# Relay_connected.net
KiCad netlist of a schematic drawn in Altium Designer
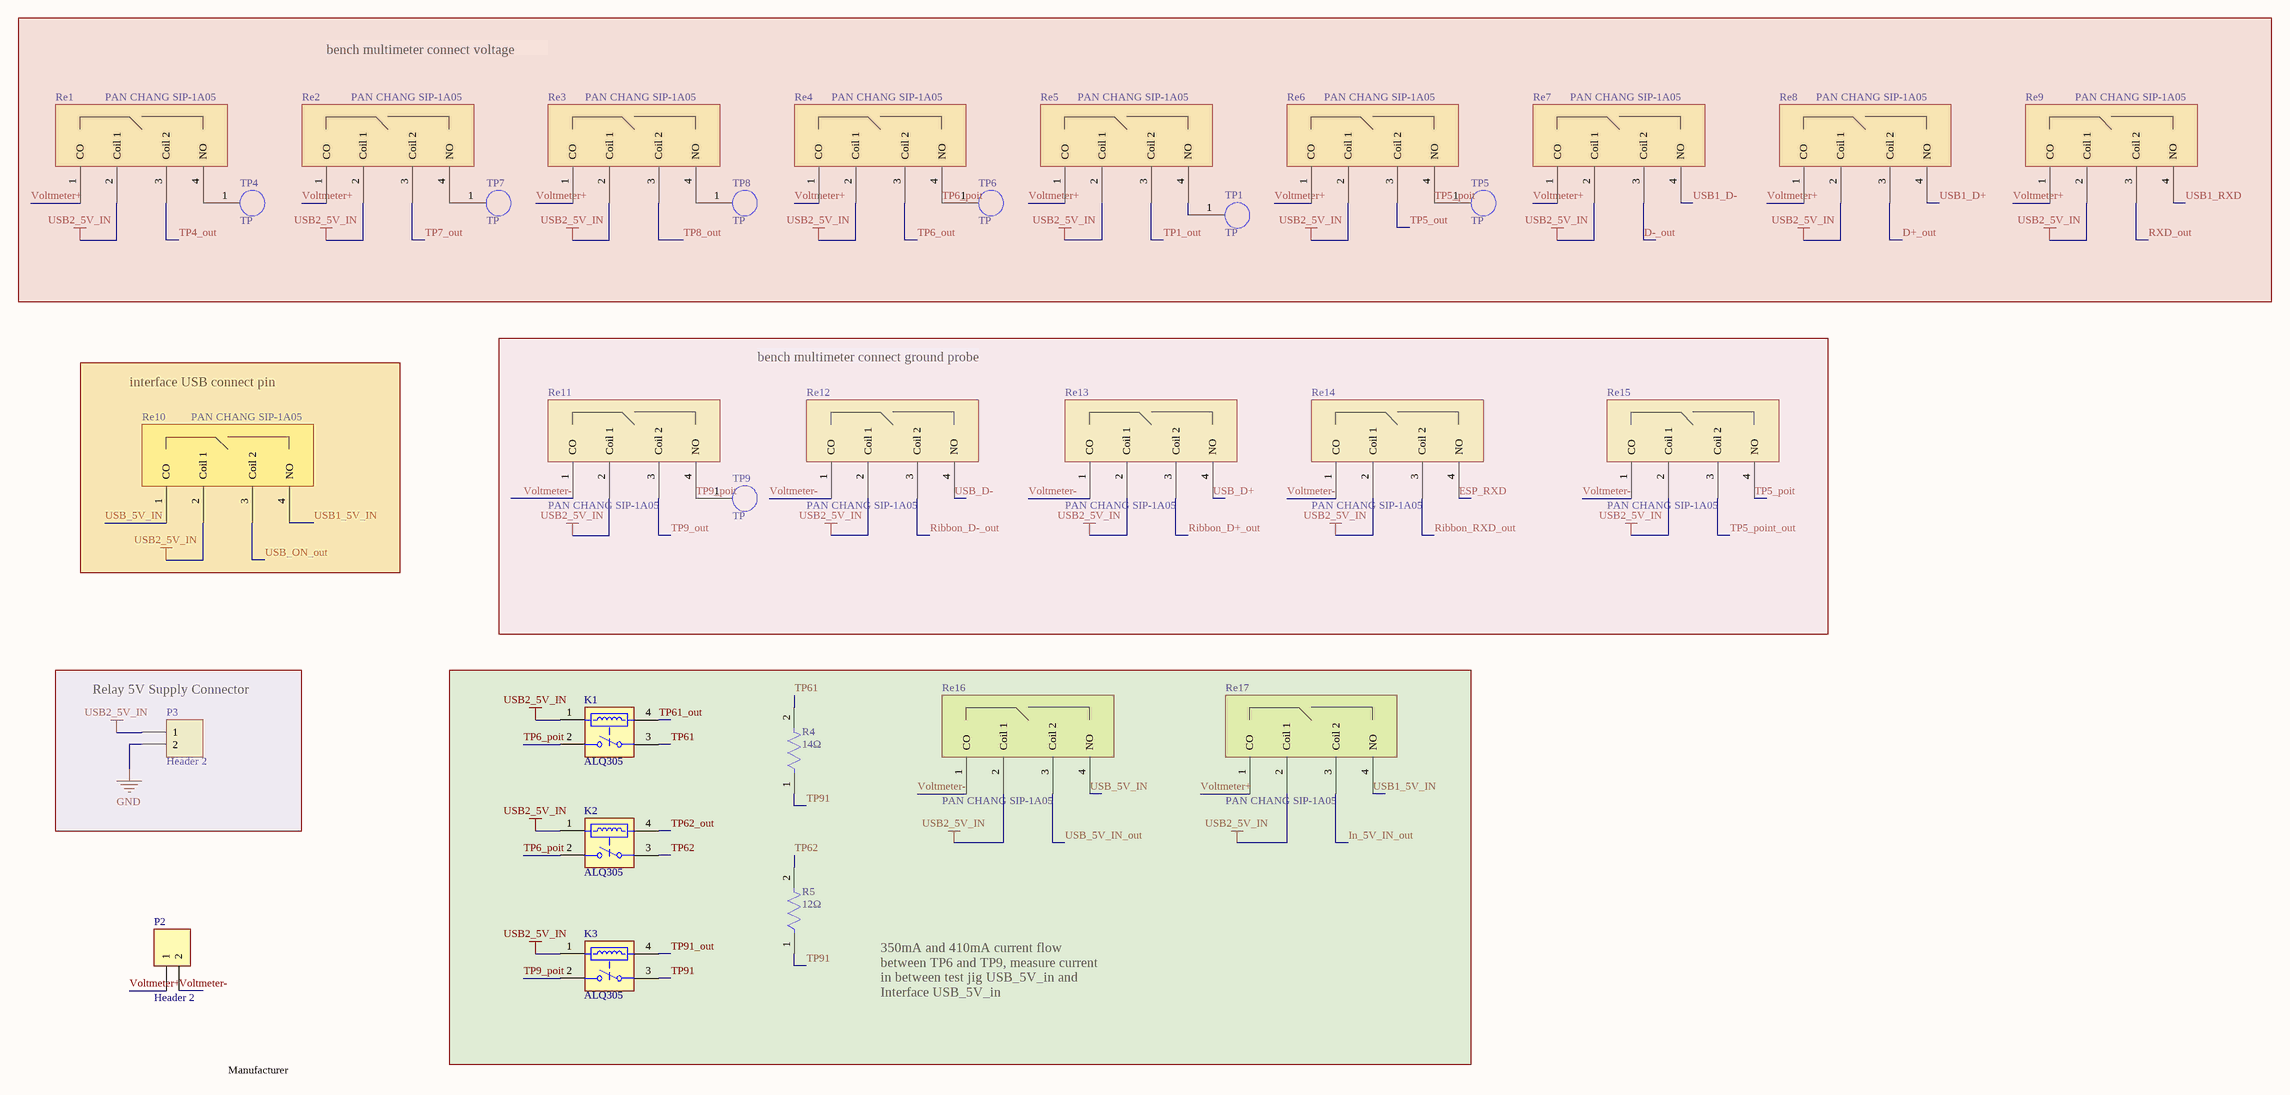
[diagram p0: Relay connected.SchDoc]

(export (version "E")
  (design (tool "Eeschema 10.0.6"))
  (components
    (comp (ref "K1")
      (value "ALQ305")
      (footprint "PNSC-LQ-4-2000x1000x1600_V")
      (fields (field (name "MANUFACTURER") "Panasonic"))
      (libsource (lib "Altium Content Vault") (part "PNSC-ALQ305-LQ-4-2000x1000x1600-4"))
    )
    (comp (ref "K2")
      (value "ALQ305")
      (footprint "PNSC-LQ-4-2000x1000x1600_V")
      (fields (field (name "MANUFACTURER") "Panasonic"))
      (libsource (lib "Altium Content Vault") (part "PNSC-ALQ305-LQ-4-2000x1000x1600-4"))
    )
    (comp (ref "K3")
      (value "ALQ305")
      (footprint "PNSC-LQ-4-2000x1000x1600_V")
      (fields (field (name "MANUFACTURER") "Panasonic"))
      (libsource (lib "Altium Content Vault") (part "PNSC-ALQ305-LQ-4-2000x1000x1600-4"))
    )
    (comp (ref "P2")
      (value "Header 2")
      (footprint "HDR1X2")
      (description "Header, 2-Pin")
      (fields (field (name "PUBLISHER") "Altium Limited"))
      (libsource (lib "Miscellaneous Connectors") (part "Header 2"))
    )
    (comp (ref "P3")
      (value "Header 2")
      (footprint "HDR1X2")
      (description "Header, 2-Pin")
      (fields (field (name "PUBLISHER") "Altium Limited"))
      (libsource (lib "") (part "Header 2_1"))
    )
    (comp (ref "R4")
      (value "14Ω")
      (footprint "FP-CRCW0603-e3-IPC_B")
      (description "RES Thick Film, 14Ω, 1%, 0.1W, 100ppm/°C, 0603")
      (fields (field (name "TOLERANCE") "1%") (field (name "MANUFACTURER") "SEI(Stackpole Elec)"))
      (libsource (lib "Altium Content Vault") (part "1029c3af85768c4190bb7ad29bc67b5"))
    )
    (comp (ref "R5")
      (value "12Ω")
      (footprint "FP-CRCW0805-e3-IPC_C")
      (description "RES Thick Film, 12Ω, 1%, 0.125W, 100ppm/°C, 0805")
      (fields (field (name "TOLERANCE") "1%") (field (name "MANUFACTURER") "Vishay"))
      (libsource (lib "Altium Content Vault") (part "1029c3af85768c4190bb7ad29bc67b5"))
    )
    (comp (ref "Re1")
      (value "PAN CHANG SIP-1A05")
      (footprint "PAN CHANG SIP-1A05")
      (description "SPST - NO 5V DC Nolocking Through Hole Reed Relays ROHS")
      (fields (field (name "MFR. PART #") "SIP-1A05") (field (name "LCSC PART #") "C10496"))
      (libsource (lib "Relays") (part "PAN CHANG SIP-1A05"))
    )
    (comp (ref "Re2")
      (value "PAN CHANG SIP-1A05")
      (footprint "PAN CHANG SIP-1A05")
      (description "SPST - NO 5V DC Nolocking Through Hole Reed Relays ROHS")
      (fields (field (name "MFR. PART #") "SIP-1A05") (field (name "LCSC PART #") "C10496"))
      (libsource (lib "Relays") (part "PAN CHANG SIP-1A05"))
    )
    (comp (ref "Re3")
      (value "PAN CHANG SIP-1A05")
      (footprint "PAN CHANG SIP-1A05")
      (description "SPST - NO 5V DC Nolocking Through Hole Reed Relays ROHS")
      (fields (field (name "MFR. PART #") "SIP-1A05") (field (name "LCSC PART #") "C10496"))
      (libsource (lib "Relays") (part "PAN CHANG SIP-1A05"))
    )
    (comp (ref "Re4")
      (value "PAN CHANG SIP-1A05")
      (footprint "PAN CHANG SIP-1A05")
      (description "SPST - NO 5V DC Nolocking Through Hole Reed Relays ROHS")
      (fields (field (name "MFR. PART #") "SIP-1A05") (field (name "LCSC PART #") "C10496"))
      (libsource (lib "Relays") (part "PAN CHANG SIP-1A05"))
    )
    (comp (ref "Re5")
      (value "PAN CHANG SIP-1A05")
      (footprint "PAN CHANG SIP-1A05")
      (description "SPST - NO 5V DC Nolocking Through Hole Reed Relays ROHS")
      (fields (field (name "MFR. PART #") "SIP-1A05") (field (name "LCSC PART #") "C10496"))
      (libsource (lib "Relays") (part "PAN CHANG SIP-1A05"))
    )
    (comp (ref "Re6")
      (value "PAN CHANG SIP-1A05")
      (footprint "PAN CHANG SIP-1A05")
      (description "SPST - NO 5V DC Nolocking Through Hole Reed Relays ROHS")
      (fields (field (name "MFR. PART #") "SIP-1A05") (field (name "LCSC PART #") "C10496"))
      (libsource (lib "Relays") (part "PAN CHANG SIP-1A05"))
    )
    (comp (ref "Re7")
      (value "PAN CHANG SIP-1A05")
      (footprint "PAN CHANG SIP-1A05")
      (description "SPST - NO 5V DC Nolocking Through Hole Reed Relays ROHS")
      (fields (field (name "MFR. PART #") "SIP-1A05") (field (name "LCSC PART #") "C10496"))
      (libsource (lib "Relays") (part "PAN CHANG SIP-1A05"))
    )
    (comp (ref "Re8")
      (value "PAN CHANG SIP-1A05")
      (footprint "PAN CHANG SIP-1A05")
      (description "SPST - NO 5V DC Nolocking Through Hole Reed Relays ROHS")
      (fields (field (name "MFR. PART #") "SIP-1A05") (field (name "LCSC PART #") "C10496"))
      (libsource (lib "Relays") (part "PAN CHANG SIP-1A05"))
    )
    (comp (ref "Re9")
      (value "PAN CHANG SIP-1A05")
      (footprint "PAN CHANG SIP-1A05")
      (description "SPST - NO 5V DC Nolocking Through Hole Reed Relays ROHS")
      (fields (field (name "MFR. PART #") "SIP-1A05") (field (name "LCSC PART #") "C10496"))
      (libsource (lib "Relays") (part "PAN CHANG SIP-1A05"))
    )
    (comp (ref "Re10")
      (value "PAN CHANG SIP-1A05")
      (footprint "PAN CHANG SIP-1A05")
      (description "SPST - NO 5V DC Nolocking Through Hole Reed Relays ROHS")
      (fields (field (name "MFR. PART #") "SIP-1A05") (field (name "LCSC PART #") "C10496"))
      (libsource (lib "Relays") (part "PAN CHANG SIP-1A05"))
    )
    (comp (ref "Re11")
      (value "PAN CHANG SIP-1A05")
      (footprint "PAN CHANG SIP-1A05")
      (description "SPST - NO 5V DC Nolocking Through Hole Reed Relays ROHS")
      (fields (field (name "MFR. PART #") "SIP-1A05") (field (name "LCSC PART #") "C10496"))
      (libsource (lib "Relays") (part "PAN CHANG SIP-1A05"))
    )
    (comp (ref "Re12")
      (value "PAN CHANG SIP-1A05")
      (footprint "PAN CHANG SIP-1A05")
      (description "SPST - NO 5V DC Nolocking Through Hole Reed Relays ROHS")
      (fields (field (name "MFR. PART #") "SIP-1A05") (field (name "LCSC PART #") "C10496"))
      (libsource (lib "Relays") (part "PAN CHANG SIP-1A05"))
    )
    (comp (ref "Re13")
      (value "PAN CHANG SIP-1A05")
      (footprint "PAN CHANG SIP-1A05")
      (description "SPST - NO 5V DC Nolocking Through Hole Reed Relays ROHS")
      (fields (field (name "MFR. PART #") "SIP-1A05") (field (name "LCSC PART #") "C10496"))
      (libsource (lib "Relays") (part "PAN CHANG SIP-1A05"))
    )
    (comp (ref "Re14")
      (value "PAN CHANG SIP-1A05")
      (footprint "PAN CHANG SIP-1A05")
      (description "SPST - NO 5V DC Nolocking Through Hole Reed Relays ROHS")
      (fields (field (name "MFR. PART #") "SIP-1A05") (field (name "LCSC PART #") "C10496"))
      (libsource (lib "Relays") (part "PAN CHANG SIP-1A05"))
    )
    (comp (ref "Re15")
      (value "PAN CHANG SIP-1A05")
      (footprint "PAN CHANG SIP-1A05")
      (description "SPST - NO 5V DC Nolocking Through Hole Reed Relays ROHS")
      (fields (field (name "MFR. PART #") "SIP-1A05") (field (name "LCSC PART #") "C10496"))
      (libsource (lib "Relays") (part "PAN CHANG SIP-1A05"))
    )
    (comp (ref "Re16")
      (value "PAN CHANG SIP-1A05")
      (footprint "PAN CHANG SIP-1A05")
      (description "SPST - NO 5V DC Nolocking Through Hole Reed Relays ROHS")
      (fields (field (name "MFR. PART #") "SIP-1A05") (field (name "LCSC PART #") "C10496"))
      (libsource (lib "Relays") (part "PAN CHANG SIP-1A05"))
    )
    (comp (ref "Re17")
      (value "PAN CHANG SIP-1A05")
      (footprint "PAN CHANG SIP-1A05")
      (description "SPST - NO 5V DC Nolocking Through Hole Reed Relays ROHS")
      (fields (field (name "MFR. PART #") "SIP-1A05") (field (name "LCSC PART #") "C10496"))
      (libsource (lib "Relays") (part "PAN CHANG SIP-1A05"))
    )
    (comp (ref "TP1") (value "TP") (footprint "Testpoint") (libsource (lib "U-e-m5ss-y-5") (part "TP")))
    (comp (ref "TP4") (value "TP") (footprint "Testpoint") (libsource (lib "U-e-m5ss-y-5") (part "TP")))
    (comp (ref "TP5") (value "TP") (footprint "Testpoint") (libsource (lib "U-e-m5ss-y-5") (part "TP")))
    (comp (ref "TP6") (value "TP") (footprint "Testpoint") (libsource (lib "U-e-m5ss-y-5") (part "TP")))
    (comp (ref "TP7") (value "TP") (footprint "Testpoint") (libsource (lib "U-e-m5ss-y-5") (part "TP")))
    (comp (ref "TP8") (value "TP") (footprint "Testpoint") (libsource (lib "U-e-m5ss-y-5") (part "TP")))
    (comp (ref "TP9") (value "TP") (footprint "Testpoint") (libsource (lib "U-e-m5ss-y-5") (part "TP")))
  )
  (nets
    (net (code "1") (name "/D+_out") (class "Default")
      (node (ref "Re8") (pin "3") (pinfunction "Coil_2_3") (pintype "passive"))
    )
    (net (code "2") (name "/D-_out") (class "Default")
      (node (ref "Re7") (pin "3") (pinfunction "Coil_2_3") (pintype "passive"))
    )
    (net (code "3") (name "/ESP_RXD") (class "Default")
      (node (ref "Re14") (pin "4") (pinfunction "NO_4") (pintype "passive"))
    )
    (net (code "4") (name "/In_5V_IN_out") (class "Default")
      (node (ref "Re17") (pin "3") (pinfunction "Coil_2_3") (pintype "passive"))
    )
    (net (code "5") (name "/RXD_out") (class "Default")
      (node (ref "Re9") (pin "3") (pinfunction "Coil_2_3") (pintype "passive"))
    )
    (net (code "6") (name "/Ribbon_D+_out") (class "Default")
      (node (ref "Re13") (pin "3") (pinfunction "Coil_2_3") (pintype "passive"))
    )
    (net (code "7") (name "/Ribbon_D-_out") (class "Default")
      (node (ref "Re12") (pin "3") (pinfunction "Coil_2_3") (pintype "passive"))
    )
    (net (code "8") (name "/Ribbon_RXD_out") (class "Default")
      (node (ref "Re14") (pin "3") (pinfunction "Coil_2_3") (pintype "passive"))
    )
    (net (code "9") (name "/TP1_out") (class "Default")
      (node (ref "Re5") (pin "3") (pinfunction "Coil_2_3") (pintype "passive"))
    )
    (net (code "10") (name "/TP4_out") (class "Default")
      (node (ref "Re1") (pin "3") (pinfunction "Coil_2_3") (pintype "passive"))
    )
    (net (code "11") (name "/TP5_out") (class "Default")
      (node (ref "Re6") (pin "3") (pinfunction "Coil_2_3") (pintype "passive"))
    )
    (net (code "12") (name "/TP5_point_out") (class "Default")
      (node (ref "Re15") (pin "3") (pinfunction "Coil_2_3") (pintype "passive"))
    )
    (net (code "13") (name "/TP5_poit") (class "Default")
      (node (ref "Re15") (pin "4") (pinfunction "NO_4") (pintype "passive"))
      (node (ref "Re6") (pin "4") (pinfunction "NO_4") (pintype "passive"))
      (node (ref "TP5") (pin "1") (pintype "power_in"))
    )
    (net (code "14") (name "/TP6_out") (class "Default")
      (node (ref "Re4") (pin "3") (pinfunction "Coil_2_3") (pintype "passive"))
    )
    (net (code "15") (name "/TP6_poit") (class "Default")
      (node (ref "K1") (pin "2") (pinfunction "NO_2") (pintype "passive"))
      (node (ref "K2") (pin "2") (pinfunction "NO_2") (pintype "passive"))
      (node (ref "Re4") (pin "4") (pinfunction "NO_4") (pintype "passive"))
      (node (ref "TP6") (pin "1") (pintype "power_in"))
    )
    (net (code "16") (name "/TP7_out") (class "Default")
      (node (ref "Re2") (pin "3") (pinfunction "Coil_2_3") (pintype "passive"))
    )
    (net (code "17") (name "/TP8_out") (class "Default")
      (node (ref "Re3") (pin "3") (pinfunction "Coil_2_3") (pintype "passive"))
    )
    (net (code "18") (name "/TP9_out") (class "Default")
      (node (ref "Re11") (pin "3") (pinfunction "Coil_2_3") (pintype "passive"))
    )
    (net (code "19") (name "/TP9_poit") (class "Default")
      (node (ref "K3") (pin "2") (pinfunction "NO_2") (pintype "passive"))
      (node (ref "Re11") (pin "4") (pinfunction "NO_4") (pintype "passive"))
      (node (ref "TP9") (pin "1") (pintype "power_in"))
    )
    (net (code "20") (name "/TP61") (class "Default")
      (node (ref "K1") (pin "3") (pinfunction "COM_3") (pintype "passive"))
      (node (ref "R4") (pin "2") (pinfunction "2_2") (pintype "passive"))
    )
    (net (code "21") (name "/TP61_out") (class "Default")
      (node (ref "K1") (pin "4") (pinfunction "4_4") (pintype "passive"))
    )
    (net (code "22") (name "/TP62") (class "Default")
      (node (ref "K2") (pin "3") (pinfunction "COM_3") (pintype "passive"))
      (node (ref "R5") (pin "2") (pinfunction "2_2") (pintype "passive"))
    )
    (net (code "23") (name "/TP62_out") (class "Default")
      (node (ref "K2") (pin "4") (pinfunction "4_4") (pintype "passive"))
    )
    (net (code "24") (name "/TP91") (class "Default")
      (node (ref "K3") (pin "3") (pinfunction "COM_3") (pintype "passive"))
      (node (ref "R4") (pin "1") (pinfunction "1_1") (pintype "passive"))
      (node (ref "R5") (pin "1") (pinfunction "1_1") (pintype "passive"))
    )
    (net (code "25") (name "/TP91_out") (class "Default")
      (node (ref "K3") (pin "4") (pinfunction "4_4") (pintype "passive"))
    )
    (net (code "26") (name "/USB1_5V_IN") (class "Default")
      (node (ref "Re10") (pin "4") (pinfunction "NO_4") (pintype "passive"))
      (node (ref "Re17") (pin "4") (pinfunction "NO_4") (pintype "passive"))
    )
    (net (code "27") (name "/USB1_D+") (class "Default")
      (node (ref "Re8") (pin "4") (pinfunction "NO_4") (pintype "passive"))
    )
    (net (code "28") (name "/USB1_D-") (class "Default")
      (node (ref "Re7") (pin "4") (pinfunction "NO_4") (pintype "passive"))
    )
    (net (code "29") (name "/USB1_RXD") (class "Default")
      (node (ref "Re9") (pin "4") (pinfunction "NO_4") (pintype "passive"))
    )
    (net (code "30") (name "/USB_5V_IN") (class "Default")
      (node (ref "Re10") (pin "1") (pinfunction "CO_1") (pintype "passive"))
      (node (ref "Re16") (pin "4") (pinfunction "NO_4") (pintype "passive"))
    )
    (net (code "31") (name "/USB_5V_IN_out") (class "Default")
      (node (ref "Re16") (pin "3") (pinfunction "Coil_2_3") (pintype "passive"))
    )
    (net (code "32") (name "/USB_D+") (class "Default")
      (node (ref "Re13") (pin "4") (pinfunction "NO_4") (pintype "passive"))
    )
    (net (code "33") (name "/USB_D-") (class "Default")
      (node (ref "Re12") (pin "4") (pinfunction "NO_4") (pintype "passive"))
    )
    (net (code "34") (name "/USB_ON_out") (class "Default")
      (node (ref "Re10") (pin "3") (pinfunction "Coil_2_3") (pintype "passive"))
    )
    (net (code "35") (name "/Voltmeter+") (class "Default")
      (node (ref "P2") (pin "1") (pinfunction "1_1") (pintype "passive"))
      (node (ref "Re1") (pin "1") (pinfunction "CO_1") (pintype "passive"))
      (node (ref "Re17") (pin "1") (pinfunction "CO_1") (pintype "passive"))
      (node (ref "Re2") (pin "1") (pinfunction "CO_1") (pintype "passive"))
      (node (ref "Re3") (pin "1") (pinfunction "CO_1") (pintype "passive"))
      (node (ref "Re4") (pin "1") (pinfunction "CO_1") (pintype "passive"))
      (node (ref "Re5") (pin "1") (pinfunction "CO_1") (pintype "passive"))
      (node (ref "Re6") (pin "1") (pinfunction "CO_1") (pintype "passive"))
      (node (ref "Re7") (pin "1") (pinfunction "CO_1") (pintype "passive"))
      (node (ref "Re8") (pin "1") (pinfunction "CO_1") (pintype "passive"))
      (node (ref "Re9") (pin "1") (pinfunction "CO_1") (pintype "passive"))
    )
    (net (code "36") (name "/Voltmeter-") (class "Default")
      (node (ref "P2") (pin "2") (pinfunction "2_2") (pintype "passive"))
      (node (ref "Re11") (pin "1") (pinfunction "CO_1") (pintype "passive"))
      (node (ref "Re12") (pin "1") (pinfunction "CO_1") (pintype "passive"))
      (node (ref "Re13") (pin "1") (pinfunction "CO_1") (pintype "passive"))
      (node (ref "Re14") (pin "1") (pinfunction "CO_1") (pintype "passive"))
      (node (ref "Re15") (pin "1") (pinfunction "CO_1") (pintype "passive"))
      (node (ref "Re16") (pin "1") (pinfunction "CO_1") (pintype "passive"))
    )
    (net (code "37") (name "GND") (class "Default")
      (node (ref "P3") (pin "2") (pinfunction "2_2") (pintype "passive"))
    )
    (net (code "38") (name "Net-(Re1-NO)") (class "Default")
      (node (ref "Re1") (pin "4") (pinfunction "NO_4") (pintype "passive"))
      (node (ref "TP4") (pin "1") (pintype "power_in"))
    )
    (net (code "39") (name "Net-(Re2-NO)") (class "Default")
      (node (ref "Re2") (pin "4") (pinfunction "NO_4") (pintype "passive"))
      (node (ref "TP7") (pin "1") (pintype "power_in"))
    )
    (net (code "40") (name "Net-(Re3-NO)") (class "Default")
      (node (ref "Re3") (pin "4") (pinfunction "NO_4") (pintype "passive"))
      (node (ref "TP8") (pin "1") (pintype "power_in"))
    )
    (net (code "41") (name "Net-(Re5-NO)") (class "Default")
      (node (ref "Re5") (pin "4") (pinfunction "NO_4") (pintype "passive"))
      (node (ref "TP1") (pin "1") (pintype "power_in"))
    )
    (net (code "42") (name "USB2_5V_IN") (class "Default")
      (node (ref "K1") (pin "1") (pinfunction "1_1") (pintype "passive"))
      (node (ref "K2") (pin "1") (pinfunction "1_1") (pintype "passive"))
      (node (ref "K3") (pin "1") (pinfunction "1_1") (pintype "passive"))
      (node (ref "P3") (pin "1") (pinfunction "1_1") (pintype "passive"))
      (node (ref "Re1") (pin "2") (pinfunction "Coil_1_2") (pintype "passive"))
      (node (ref "Re10") (pin "2") (pinfunction "Coil_1_2") (pintype "passive"))
      (node (ref "Re11") (pin "2") (pinfunction "Coil_1_2") (pintype "passive"))
      (node (ref "Re12") (pin "2") (pinfunction "Coil_1_2") (pintype "passive"))
      (node (ref "Re13") (pin "2") (pinfunction "Coil_1_2") (pintype "passive"))
      (node (ref "Re14") (pin "2") (pinfunction "Coil_1_2") (pintype "passive"))
      (node (ref "Re15") (pin "2") (pinfunction "Coil_1_2") (pintype "passive"))
      (node (ref "Re16") (pin "2") (pinfunction "Coil_1_2") (pintype "passive"))
      (node (ref "Re17") (pin "2") (pinfunction "Coil_1_2") (pintype "passive"))
      (node (ref "Re2") (pin "2") (pinfunction "Coil_1_2") (pintype "passive"))
      (node (ref "Re3") (pin "2") (pinfunction "Coil_1_2") (pintype "passive"))
      (node (ref "Re4") (pin "2") (pinfunction "Coil_1_2") (pintype "passive"))
      (node (ref "Re5") (pin "2") (pinfunction "Coil_1_2") (pintype "passive"))
      (node (ref "Re6") (pin "2") (pinfunction "Coil_1_2") (pintype "passive"))
      (node (ref "Re7") (pin "2") (pinfunction "Coil_1_2") (pintype "passive"))
      (node (ref "Re8") (pin "2") (pinfunction "Coil_1_2") (pintype "passive"))
      (node (ref "Re9") (pin "2") (pinfunction "Coil_1_2") (pintype "passive"))
    )
  )
)
